# FuenteAlimentacion.net
KiCad netlist of a schematic drawn in Altium Designer
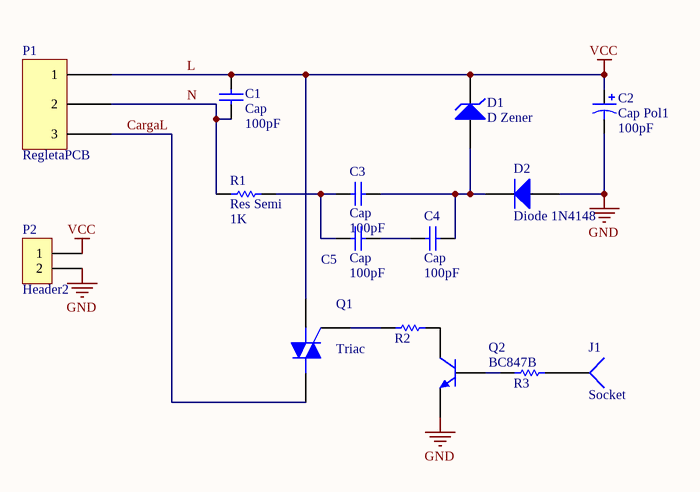
[diagram p0: FuenteAlimentacion.SchDoc]

(export (version "E")
  (design (tool "Eeschema 10.0.6"))
  (components
    (comp (ref "C1")
      (value "Cap")
      (footprint "CAPR5.08-7.8x3.2")
      (description "Capacitor")
      (fields (field (name "ALTIUM_VALUE") "100pF") (field (name "PUBLISHER") "Altium Limited"))
      (libsource (lib "Miscellaneous Devices") (part "Cap"))
    )
    (comp (ref "C2")
      (value "Cap Pol1")
      (footprint "CAPPR2-5x6.8")
      (description "Polarized Capacitor (Radial)")
      (fields (field (name "ALTIUM_VALUE") "100pF") (field (name "PUBLISHER") "Altium Limited"))
      (libsource (lib "Miscellaneous Devices") (part "Cap Pol1"))
    )
    (comp (ref "C3")
      (value "Cap")
      (footprint "CAP400V")
      (description "Capacitor")
      (fields (field (name "ALTIUM_VALUE") "100pF") (field (name "PUBLISHER") "Altium Limited"))
      (libsource (lib "Miscellaneous Devices") (part "Cap"))
    )
    (comp (ref "C4")
      (value "Cap")
      (footprint "CAP250V")
      (description "Capacitor")
      (fields (field (name "ALTIUM_VALUE") "100pF") (field (name "PUBLISHER") "Altium Limited"))
      (libsource (lib "Miscellaneous Devices") (part "Cap"))
    )
    (comp (ref "C5")
      (value "Cap")
      (footprint "CAP250V")
      (description "Capacitor")
      (fields (field (name "ALTIUM_VALUE") "100pF") (field (name "PUBLISHER") "Altium Limited"))
      (libsource (lib "Miscellaneous Devices") (part "Cap"))
    )
    (comp (ref "D1")
      (value "D Zener")
      (footprint "Zener")
      (description "Zener Diode")
      (fields (field (name "PUBLISHER") "Altium Limited"))
      (libsource (lib "Miscellaneous Devices") (part "D Zener"))
    )
    (comp (ref "D2")
      (value "Diode 1N4148")
      (footprint "1N4148SMD")
      (description "High Conductance Fast Diode")
      (fields (field (name "PUBLISHER") "Altium Limited"))
      (libsource (lib "Miscellaneous Devices") (part "Diode 1N4148"))
    )
    (comp (ref "J1")
      (value "Socket")
      (footprint "PIN1")
      (fields (field (name "PUBLISHER") "Altium Limited"))
      (libsource (lib "Miscellaneous Connectors") (part "Socket"))
    )
    (comp (ref "P1")
      (value "RegletaPCB")
      (footprint "RegletaPCBx3")
      (libsource (lib "epf") (part "RegletaPCBx3"))
    )
    (comp (ref "P2") (value "Header2") (footprint "Header2Macho") (libsource (lib "epf") (part "Header2")))
    (comp (ref "Q1")
      (value "Triac")
      (footprint "SFM-T3/A2.4V")
      (description "Silicon Bidirectional Triode Thyristor")
      (fields (field (name "PUBLISHER") "Altium Limited"))
      (libsource (lib "Miscellaneous Devices") (part "Triac"))
    )
    (comp (ref "Q2")
      (value "BC847B")
      (footprint "SOT23_N")
      (description "NPN General-purpose Transistor")
      (fields (field (name "PUBLISHER") "Altium Limited"))
      (libsource (lib "Philips Discrete BJT - Low Power") (part "BC847B"))
    )
    (comp (ref "R1")
      (value "Res Semi")
      (footprint "AXIAL-0.5")
      (description "Semiconductor Resistor")
      (fields (field (name "ALTIUM_VALUE") "1K") (field (name "PUBLISHER") "Altium Limited"))
      (libsource (lib "Miscellaneous Devices") (part "Res Semi"))
    )
    (comp (ref "R2") (value "Resistor") (footprint "0805_RES") (libsource (lib "epf") (part "Res")))
    (comp (ref "R3") (value "Resistor") (footprint "0805_RES") (libsource (lib "epf") (part "Res")))
  )
  (nets
    (net (code "1") (name "/CargaL") (class "Default")
      (node (ref "P1") (pin "3") (pinfunction "3_3") (pintype "passive"))
      (node (ref "Q1") (pin "2") (pinfunction "M2_2") (pintype "passive"))
    )
    (net (code "2") (name "/N") (class "Default")
      (node (ref "C1") (pin "1") (pinfunction "1_1") (pintype "passive"))
      (node (ref "P1") (pin "2") (pinfunction "2_2") (pintype "passive"))
      (node (ref "R1") (pin "1") (pinfunction "1_1") (pintype "passive"))
    )
    (net (code "3") (name "GND") (class "Default")
      (node (ref "C2") (pin "2") (pinfunction "2_2") (pintype "passive"))
      (node (ref "D2") (pin "1") (pinfunction "A_1") (pintype "passive"))
      (node (ref "P2") (pin "2") (pinfunction "2_2") (pintype "passive"))
      (node (ref "Q2") (pin "2") (pinfunction "E_2") (pintype "passive"))
    )
    (net (code "4") (name "Net-(C3-Pad1)") (class "Default")
      (node (ref "C3") (pin "1") (pinfunction "1_1") (pintype "passive"))
      (node (ref "C5") (pin "1") (pinfunction "1_1") (pintype "passive"))
      (node (ref "R1") (pin "2") (pinfunction "2_2") (pintype "passive"))
    )
    (net (code "5") (name "Net-(C4-Pad1)") (class "Default")
      (node (ref "C4") (pin "1") (pinfunction "1_1") (pintype "passive"))
      (node (ref "C5") (pin "2") (pinfunction "2_2") (pintype "passive"))
    )
    (net (code "6") (name "Net-(D1-A)") (class "Default")
      (node (ref "C3") (pin "2") (pinfunction "2_2") (pintype "passive"))
      (node (ref "C4") (pin "2") (pinfunction "2_2") (pintype "passive"))
      (node (ref "D1") (pin "1") (pinfunction "A_1") (pintype "passive"))
      (node (ref "D2") (pin "2") (pinfunction "K_2") (pintype "passive"))
    )
    (net (code "7") (name "Net-(J1-Pad1)") (class "Default")
      (node (ref "J1") (pin "1") (pinfunction "1_1") (pintype "passive"))
      (node (ref "R3") (pin "2") (pinfunction "2_2") (pintype "passive"))
    )
    (net (code "8") (name "Net-(Q1-G)") (class "Default")
      (node (ref "Q1") (pin "3") (pinfunction "G_3") (pintype "passive"))
      (node (ref "R2") (pin "1") (pinfunction "1_1") (pintype "passive"))
    )
    (net (code "9") (name "Net-(Q2-B)") (class "Default")
      (node (ref "Q2") (pin "1") (pinfunction "B_1") (pintype "passive"))
      (node (ref "R3") (pin "1") (pinfunction "1_1") (pintype "passive"))
    )
    (net (code "10") (name "Net-(Q2-C)") (class "Default")
      (node (ref "Q2") (pin "3") (pinfunction "C_3") (pintype "passive"))
      (node (ref "R2") (pin "2") (pinfunction "2_2") (pintype "passive"))
    )
    (net (code "11") (name "VCC") (class "Default")
      (node (ref "C1") (pin "2") (pinfunction "2_2") (pintype "passive"))
      (node (ref "C2") (pin "1") (pinfunction "1_1") (pintype "passive"))
      (node (ref "D1") (pin "2") (pinfunction "K_2") (pintype "passive"))
      (node (ref "P1") (pin "1") (pinfunction "1_1") (pintype "passive"))
      (node (ref "P2") (pin "1") (pinfunction "1_1") (pintype "passive"))
      (node (ref "Q1") (pin "1") (pinfunction "M1_1") (pintype "passive"))
    )
  )
)
